# main_shema.net
KiCad netlist of a schematic drawn in EAGLE
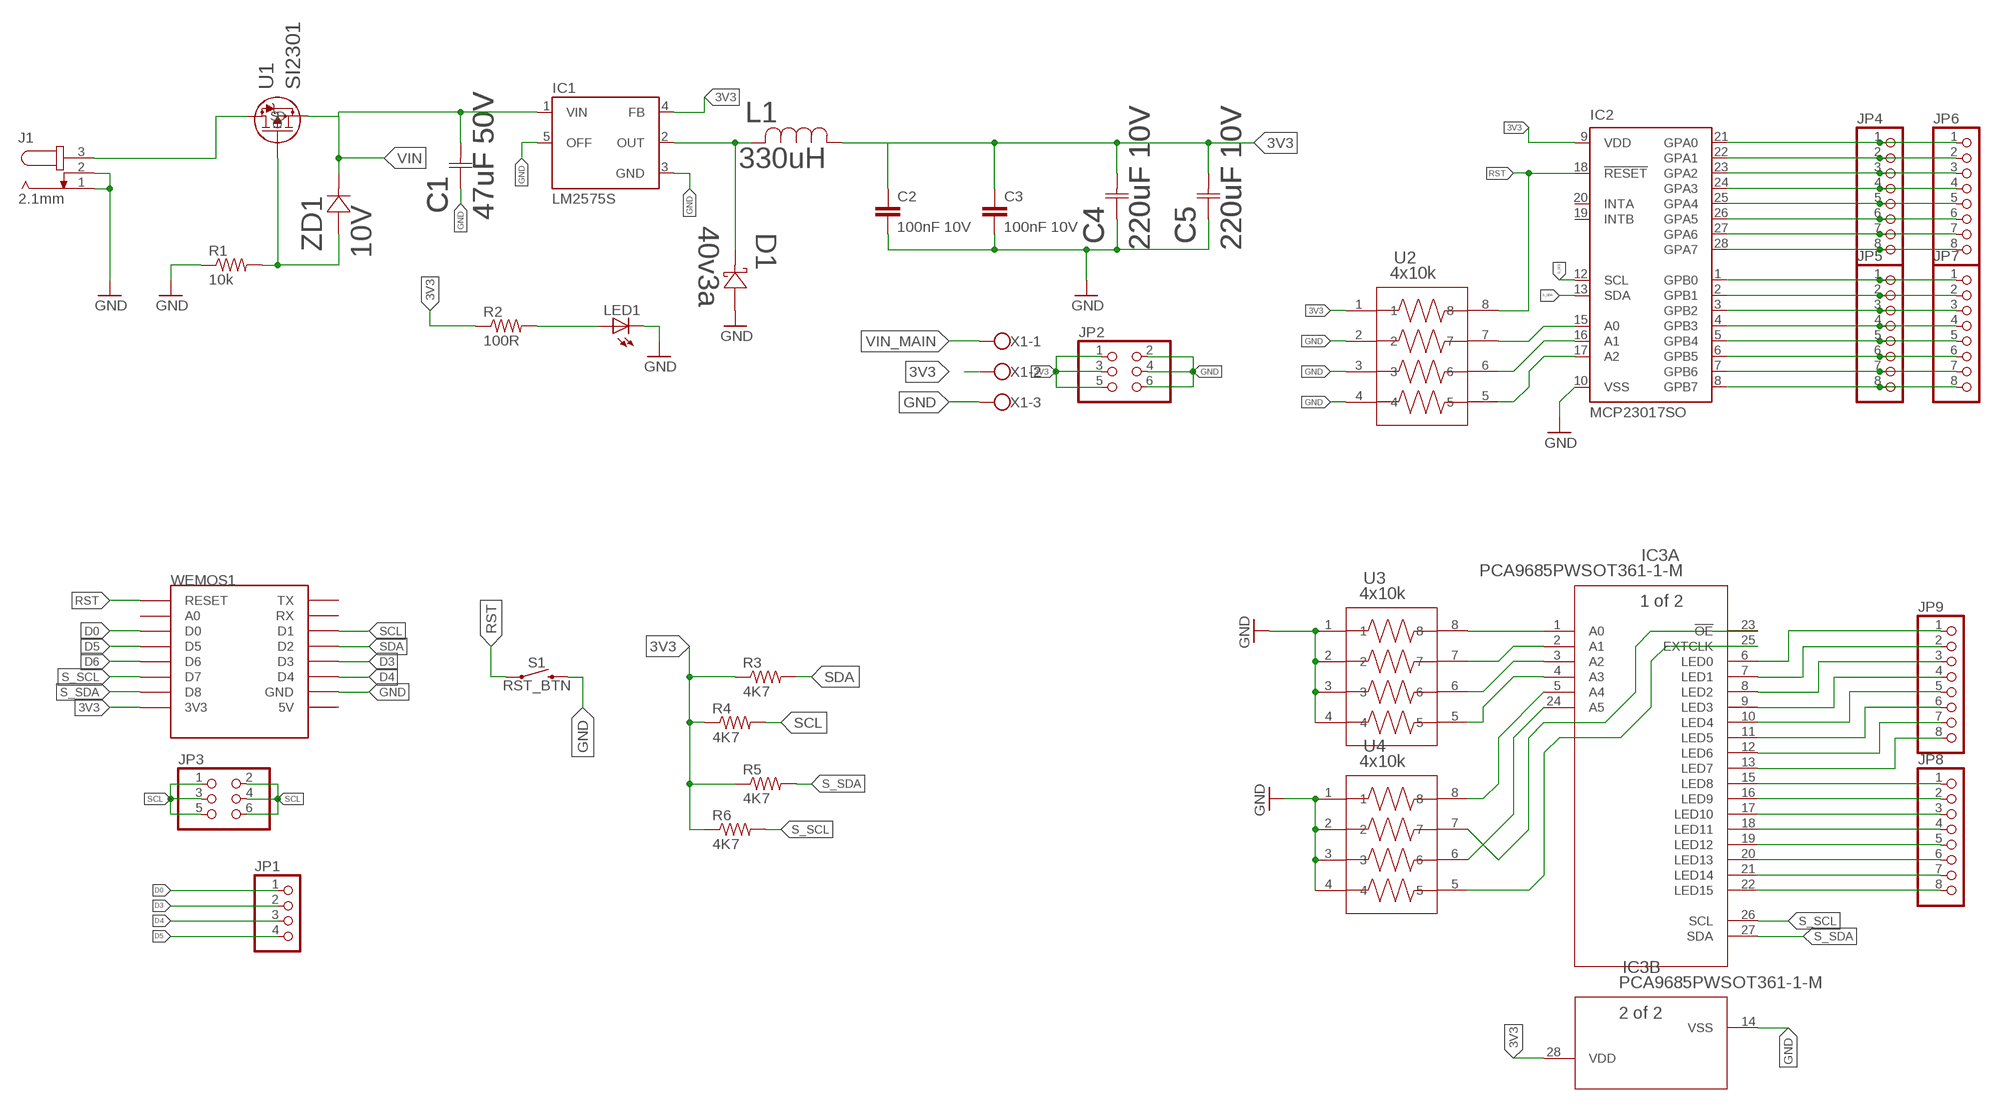
[diagram p0: schematic, sheet 1, part 1 of 2]
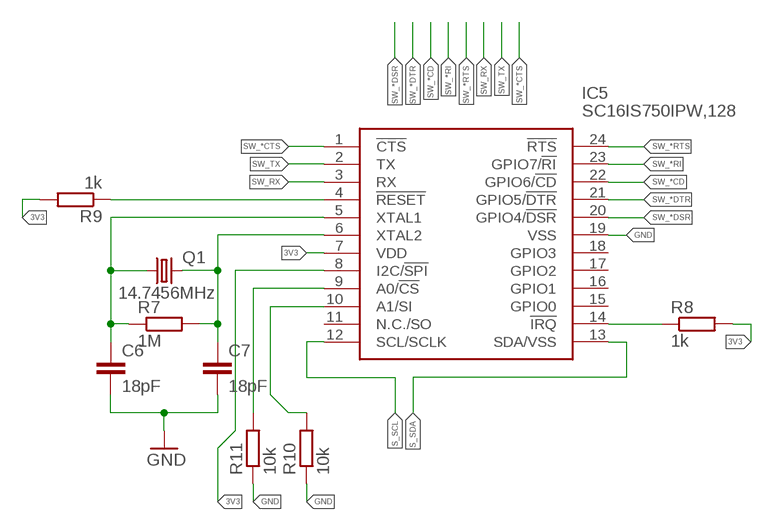
[diagram p1: schematic, sheet 1, part 2 of 2]

(export (version "E")
  (design (tool "Eeschema 10.0.6"))
  (components
    (comp (ref "C1")
      (value "47uF 50V")
      (footprint "eagle-import:CAP_EEE_D8-M")
      (fields (field (name "MANUFACTURER_PART_NUMBER") "EEE1HA470XP"))
      (libsource (lib "eagle-import") (part "EEE-1HA470XPCAP_EEE_D8-M"))
    )
    (comp (ref "C2")
      (value "100nF 10V")
      (footprint "eagle-import:C0603")
      (libsource (lib "eagle-import") (part "C-EUC0603"))
    )
    (comp (ref "C3")
      (value "100nF 10V")
      (footprint "eagle-import:C0603")
      (libsource (lib "eagle-import") (part "C-EUC0603"))
    )
    (comp (ref "C4")
      (value "220uF 10V")
      (footprint "eagle-import:CAP_EEE_D-M")
      (fields (field (name "MANUFACTURER_PART_NUMBER") "EEE0JA221WP"))
      (libsource (lib "eagle-import") (part "EEE-0JA221WPCAP_EEE_D-M"))
    )
    (comp (ref "C5")
      (value "220uF 10V")
      (footprint "eagle-import:CAP_EEE_D-M")
      (fields (field (name "MANUFACTURER_PART_NUMBER") "EEE0JA221WP"))
      (libsource (lib "eagle-import") (part "EEE-0JA221WPCAP_EEE_D-M"))
    )
    (comp (ref "C6")
      (value "18pF")
      (footprint "eagle-import:0402-CAP")
      (libsource (lib "eagle-import") (part "CAP0402-CAP"))
    )
    (comp (ref "C7")
      (value "18pF")
      (footprint "eagle-import:0402-CAP")
      (libsource (lib "eagle-import") (part "CAP0402-CAP"))
    )
    (comp (ref "D1")
      (value "40v3a")
      (footprint "eagle-import:CDBA-HF-M")
      (fields (field (name "MANUFACTURER_PART_NUMBER") "CDBA340HF"))
      (libsource (lib "eagle-import") (part "CDBA340-HFCDBA-HF-M"))
    )
    (comp (ref "IC1")
      (value "LM2575S")
      (footprint "eagle-import:TO263-5")
      (libsource (lib "eagle-import") (part "LM2575S"))
    )
    (comp (ref "IC2")
      (value "MCP23017SO")
      (footprint "eagle-import:SO28W")
      (fields (field (name "MF") "MICROCHIP") (field (name "MPN") "MCP23017-E/SO"))
      (libsource (lib "eagle-import") (part "MCP23017SO"))
    )
    (comp (ref "IC3")
      (value "PCA9685PWSOT361-1-M")
      (footprint "eagle-import:SOT361-1-M")
      (fields (field (name "MANUFACTURER_PART_NUMBER") "PCA9685PW"))
      (libsource (lib "eagle-import") (part "PCA9685PWSOT361-1-M"))
    )
    (comp (ref "IC5")
      (value "SC16IS750IPW,128")
      (footprint "eagle-import:SOP65P640X110-24N")
      (libsource (lib "eagle-import") (part "SC16IS750IPW,128"))
    )
    (comp (ref "J1")
      (value "2.1mm")
      (footprint "eagle-import:SPC4078")
      (libsource (lib "eagle-import") (part "JACK-PLUG1"))
    )
    (comp (ref "JP1")
      (value "PINHD-1X4")
      (footprint "eagle-import:1X04")
      (libsource (lib "eagle-import") (part "PINHD-1X4"))
    )
    (comp (ref "JP2")
      (value "PINHD-2X3")
      (footprint "eagle-import:2X03")
      (libsource (lib "eagle-import") (part "PINHD-2X3"))
    )
    (comp (ref "JP3")
      (value "PINHD-2X3")
      (footprint "eagle-import:2X03")
      (libsource (lib "eagle-import") (part "PINHD-2X3"))
    )
    (comp (ref "JP4")
      (value "PINHD-1X8")
      (footprint "eagle-import:1X08")
      (libsource (lib "eagle-import") (part "PINHD-1X8"))
    )
    (comp (ref "JP5")
      (value "PINHD-1X8")
      (footprint "eagle-import:1X08")
      (libsource (lib "eagle-import") (part "PINHD-1X8"))
    )
    (comp (ref "JP6")
      (value "PINHD-1X8")
      (footprint "eagle-import:1X08")
      (libsource (lib "eagle-import") (part "PINHD-1X8"))
    )
    (comp (ref "JP7")
      (value "PINHD-1X8")
      (footprint "eagle-import:1X08")
      (libsource (lib "eagle-import") (part "PINHD-1X8"))
    )
    (comp (ref "JP8")
      (value "PINHD-1X8/LONG")
      (footprint "eagle-import:1X08")
      (libsource (lib "eagle-import") (part "PINHD-1X8/LONG"))
    )
    (comp (ref "JP9")
      (value "PINHD-1X8/LONG")
      (footprint "eagle-import:1X08")
      (libsource (lib "eagle-import") (part "PINHD-1X8/LONG"))
    )
    (comp (ref "L1")
      (value "330uH")
      (footprint "eagle-import:IND_BOURNS_SRR1280")
      (fields (field (name "MANUFACTURER_PART_NUMBER") "SRR1280331K"))
      (libsource (lib "eagle-import") (part "SRR1280-331K"))
    )
    (comp (ref "LED1")
      (value "LED_E")
      (footprint "eagle-import:LED_1206")
      (libsource (lib "eagle-import") (part "LED_E"))
    )
    (comp (ref "Q1")
      (value "14.7456MHz")
      (footprint "eagle-import:CRYSTAL-SMD-5X3")
      (libsource (lib "eagle-import") (part "CRYSTAL5X3"))
    )
    (comp (ref "R1")
      (value "10k")
      (footprint "eagle-import:R0603")
      (libsource (lib "eagle-import") (part "R-US_R0603"))
    )
    (comp (ref "R2")
      (value "100R")
      (footprint "eagle-import:R0603")
      (libsource (lib "eagle-import") (part "R-US_R0603"))
    )
    (comp (ref "R3")
      (value "4K7")
      (footprint "eagle-import:R0603")
      (libsource (lib "eagle-import") (part "R-US_R0603"))
    )
    (comp (ref "R4")
      (value "4K7")
      (footprint "eagle-import:R0603")
      (libsource (lib "eagle-import") (part "R-US_R0603"))
    )
    (comp (ref "R5")
      (value "4K7")
      (footprint "eagle-import:R0603")
      (libsource (lib "eagle-import") (part "R-US_R0603"))
    )
    (comp (ref "R6")
      (value "4K7")
      (footprint "eagle-import:R0603")
      (libsource (lib "eagle-import") (part "R-US_R0603"))
    )
    (comp (ref "R7")
      (value "1M")
      (footprint "eagle-import:R0402")
      (libsource (lib "eagle-import") (part "R-EU_R0402"))
    )
    (comp (ref "R8")
      (value "1k")
      (footprint "eagle-import:R0402")
      (libsource (lib "eagle-import") (part "R-EU_R0402"))
    )
    (comp (ref "R9")
      (value "1k")
      (footprint "eagle-import:R0402")
      (libsource (lib "eagle-import") (part "R-EU_R0402"))
    )
    (comp (ref "R10")
      (value "10k")
      (footprint "eagle-import:R0402")
      (libsource (lib "eagle-import") (part "R-EU_R0402"))
    )
    (comp (ref "R11")
      (value "10k")
      (footprint "eagle-import:R0402")
      (libsource (lib "eagle-import") (part "R-EU_R0402"))
    )
    (comp (ref "S1")
      (value "RST_BTN")
      (footprint "eagle-import:TACTILE_SWITCH_PTH_6.0MM")
      (libsource (lib "eagle-import") (part "MOMENTARY-SWITCH-SPST-PTH-6.0MM"))
    )
    (comp (ref "U1")
      (value "SI2301")
      (footprint "eagle-import:TO-236-M")
      (fields (field (name "MANUFACTURER_PART_NUMBER") "SI2301CDST1GE3"))
      (libsource (lib "eagle-import") (part "SI2301CDS-T1-GE3TO-236-M"))
    )
    (comp (ref "U2")
      (value "4x10k")
      (footprint "eagle-import:C_ARRAY_EXB38V")
      (fields (field (name "MANUFACTURER_PART_NUMBER") "EXB38V103JV"))
      (libsource (lib "eagle-import") (part "EXB-38V103JV"))
    )
    (comp (ref "U3")
      (value "4x10k")
      (footprint "eagle-import:C_ARRAY_EXB38V-M")
      (fields (field (name "MANUFACTURER_PART_NUMBER") "EXB38V103JV"))
      (libsource (lib "eagle-import") (part "EXB-38V103JVC_ARRAY_EXB38V-M"))
    )
    (comp (ref "U4")
      (value "4x10k")
      (footprint "eagle-import:C_ARRAY_EXB38V-M")
      (fields (field (name "MANUFACTURER_PART_NUMBER") "EXB38V103JV"))
      (libsource (lib "eagle-import") (part "EXB-38V103JVC_ARRAY_EXB38V-M"))
    )
    (comp (ref "WEMOS1")
      (value "WEMOS-D1-MINI")
      (footprint "eagle-import:WEMOS-D1-MINI")
      (libsource (lib "eagle-import") (part "WEMOS-D1-MINI"))
    )
    (comp (ref "X1")
      (value "W237-103")
      (footprint "eagle-import:W237-103")
      (fields (field (name "MPN") "237-103"))
      (libsource (lib "eagle-import") (part "W237-103"))
    )
    (comp (ref "ZD1")
      (value "10V")
      (footprint "eagle-import:SMINI2-F5-B-M")
      (fields (field (name "MANUFACTURER_PART_NUMBER") "DZ2J100M0L"))
      (libsource (lib "eagle-import") (part "DZ2J100M0LSMINI2-F5-B-M"))
    )
  )
  (nets
    (net (code "1") (name "3V3") (class "Default")
      (node (ref "C2") (pin "1") (pinfunction "1_1") (pintype "passive"))
      (node (ref "C3") (pin "1") (pinfunction "1_1") (pintype "passive"))
      (node (ref "C4") (pin "2") (pinfunction "22_2") (pintype "passive"))
      (node (ref "C5") (pin "2") (pinfunction "22_2") (pintype "passive"))
      (node (ref "IC1") (pin "4") (pinfunction "FB_4") (pintype "input"))
      (node (ref "IC2") (pin "9") (pinfunction "VDD_9") (pintype "power_in"))
      (node (ref "IC3") (pin "28") (pinfunction "VDD_28") (pintype "passive"))
      (node (ref "IC5") (pin "7") (pinfunction "VDD_7") (pintype "power_in"))
      (node (ref "IC5") (pin "8") (pinfunction "I2C/~{SPI}_8") (pintype "bidirectional"))
      (node (ref "JP2") (pin "1") (pinfunction "1_1") (pintype "passive"))
      (node (ref "JP2") (pin "3") (pinfunction "3_3") (pintype "passive"))
      (node (ref "JP2") (pin "5") (pinfunction "5_5") (pintype "passive"))
      (node (ref "L1") (pin "1") (pinfunction "1_1") (pintype "passive"))
      (node (ref "R2") (pin "1") (pinfunction "1_1") (pintype "passive"))
      (node (ref "R3") (pin "1") (pinfunction "1_1") (pintype "passive"))
      (node (ref "R4") (pin "1") (pinfunction "1_1") (pintype "passive"))
      (node (ref "R5") (pin "1") (pinfunction "1_1") (pintype "passive"))
      (node (ref "R6") (pin "1") (pinfunction "1_1") (pintype "passive"))
      (node (ref "R8") (pin "2") (pinfunction "2_2") (pintype "passive"))
      (node (ref "R9") (pin "2") (pinfunction "2_2") (pintype "passive"))
      (node (ref "U2") (pin "1") (pinfunction "1_1") (pintype "passive"))
      (node (ref "WEMOS1") (pin "3V3") (pinfunction "3V3_3V3") (pintype "bidirectional"))
      (node (ref "X1") (pin "2") (pinfunction "KL_2") (pintype "passive"))
    )
    (net (code "2") (name "D0") (class "Default")
      (node (ref "JP1") (pin "1") (pinfunction "1_1") (pintype "passive"))
      (node (ref "WEMOS1") (pin "D0") (pinfunction "D0_D0") (pintype "bidirectional"))
    )
    (net (code "3") (name "D3") (class "Default")
      (node (ref "JP1") (pin "2") (pinfunction "2_2") (pintype "passive"))
      (node (ref "WEMOS1") (pin "D3") (pinfunction "D3_D3") (pintype "bidirectional"))
    )
    (net (code "4") (name "D4") (class "Default")
      (node (ref "JP1") (pin "3") (pinfunction "3_3") (pintype "passive"))
      (node (ref "WEMOS1") (pin "D4") (pinfunction "D4_D4") (pintype "bidirectional"))
    )
    (net (code "5") (name "D5") (class "Default")
      (node (ref "JP1") (pin "4") (pinfunction "4_4") (pintype "passive"))
      (node (ref "WEMOS1") (pin "D5") (pinfunction "D5_D5") (pintype "bidirectional"))
    )
    (net (code "6") (name "D6") (class "Default")
      (node (ref "WEMOS1") (pin "D6") (pinfunction "D6_D6") (pintype "bidirectional"))
    )
    (net (code "7") (name "GND") (class "Default")
      (node (ref "C1") (pin "1") (pinfunction "11_1") (pintype "passive"))
      (node (ref "C2") (pin "2") (pinfunction "2_2") (pintype "passive"))
      (node (ref "C3") (pin "2") (pinfunction "2_2") (pintype "passive"))
      (node (ref "C4") (pin "1") (pinfunction "11_1") (pintype "passive"))
      (node (ref "C5") (pin "1") (pinfunction "11_1") (pintype "passive"))
      (node (ref "C6") (pin "2") (pinfunction "2_2") (pintype "passive"))
      (node (ref "C7") (pin "2") (pinfunction "2_2") (pintype "passive"))
      (node (ref "D1") (pin "2") (pinfunction "22_2") (pintype "passive"))
      (node (ref "IC1") (pin "3") (pinfunction "GND_3") (pintype "power_in"))
      (node (ref "IC1") (pin "5") (pinfunction "OFF_5") (pintype "input"))
      (node (ref "IC2") (pin "10") (pinfunction "VSS_10") (pintype "power_in"))
      (node (ref "IC3") (pin "14") (pinfunction "VSS_14") (pintype "passive"))
      (node (ref "IC5") (pin "19") (pinfunction "VSS_19") (pintype "bidirectional"))
      (node (ref "J1") (pin "1") (pinfunction "1_1") (pintype "passive"))
      (node (ref "J1") (pin "2") (pinfunction "2_2") (pintype "passive"))
      (node (ref "JP2") (pin "2") (pinfunction "2_2") (pintype "passive"))
      (node (ref "JP2") (pin "4") (pinfunction "4_4") (pintype "passive"))
      (node (ref "JP2") (pin "6") (pinfunction "6_6") (pintype "passive"))
      (node (ref "LED1") (pin "C") (pinfunction "C_C") (pintype "passive"))
      (node (ref "R1") (pin "1") (pinfunction "1_1") (pintype "passive"))
      (node (ref "R10") (pin "1") (pinfunction "1_1") (pintype "passive"))
      (node (ref "R11") (pin "1") (pinfunction "1_1") (pintype "passive"))
      (node (ref "S1") (pin "3") (pinfunction "2_3") (pintype "passive"))
      (node (ref "U2") (pin "2") (pinfunction "2_2") (pintype "passive"))
      (node (ref "U2") (pin "3") (pinfunction "3_3") (pintype "passive"))
      (node (ref "U2") (pin "4") (pinfunction "4_4") (pintype "passive"))
      (node (ref "U3") (pin "1") (pinfunction "1_1") (pintype "passive"))
      (node (ref "U3") (pin "2") (pinfunction "2_2") (pintype "passive"))
      (node (ref "U3") (pin "3") (pinfunction "3_3") (pintype "passive"))
      (node (ref "U3") (pin "4") (pinfunction "4_4") (pintype "passive"))
      (node (ref "U4") (pin "1") (pinfunction "1_1") (pintype "passive"))
      (node (ref "U4") (pin "2") (pinfunction "2_2") (pintype "passive"))
      (node (ref "U4") (pin "3") (pinfunction "3_3") (pintype "passive"))
      (node (ref "U4") (pin "4") (pinfunction "4_4") (pintype "passive"))
      (node (ref "WEMOS1") (pin "GND") (pinfunction "GND_GND") (pintype "bidirectional"))
      (node (ref "X1") (pin "3") (pinfunction "KL_3") (pintype "passive"))
    )
    (net (code "8") (name "Net-(D1-11)") (class "Default")
      (node (ref "D1") (pin "1") (pinfunction "11_1") (pintype "passive"))
      (node (ref "IC1") (pin "2") (pinfunction "OUT_2") (pintype "output"))
      (node (ref "L1") (pin "2") (pinfunction "2_2") (pintype "passive"))
    )
    (net (code "9") (name "Net-(IC2-A0)") (class "Default")
      (node (ref "IC2") (pin "15") (pinfunction "A0_15") (pintype "input"))
      (node (ref "U2") (pin "7") (pinfunction "7_7") (pintype "passive"))
    )
    (net (code "10") (name "Net-(IC2-A1)") (class "Default")
      (node (ref "IC2") (pin "16") (pinfunction "A1_16") (pintype "input"))
      (node (ref "U2") (pin "6") (pinfunction "6_6") (pintype "passive"))
    )
    (net (code "11") (name "Net-(IC2-A2)") (class "Default")
      (node (ref "IC2") (pin "17") (pinfunction "A2_17") (pintype "input"))
      (node (ref "U2") (pin "5") (pinfunction "5_5") (pintype "passive"))
    )
    (net (code "12") (name "Net-(IC2-GPA0)") (class "Default")
      (node (ref "IC2") (pin "21") (pinfunction "GPA0_21") (pintype "bidirectional"))
      (node (ref "JP4") (pin "1") (pinfunction "1_1") (pintype "passive"))
      (node (ref "JP6") (pin "1") (pinfunction "1_1") (pintype "passive"))
    )
    (net (code "13") (name "Net-(IC2-GPA1)") (class "Default")
      (node (ref "IC2") (pin "22") (pinfunction "GPA1_22") (pintype "bidirectional"))
      (node (ref "JP4") (pin "2") (pinfunction "2_2") (pintype "passive"))
      (node (ref "JP6") (pin "2") (pinfunction "2_2") (pintype "passive"))
    )
    (net (code "14") (name "Net-(IC2-GPA2)") (class "Default")
      (node (ref "IC2") (pin "23") (pinfunction "GPA2_23") (pintype "bidirectional"))
      (node (ref "JP4") (pin "3") (pinfunction "3_3") (pintype "passive"))
      (node (ref "JP6") (pin "3") (pinfunction "3_3") (pintype "passive"))
    )
    (net (code "15") (name "Net-(IC2-GPA3)") (class "Default")
      (node (ref "IC2") (pin "24") (pinfunction "GPA3_24") (pintype "bidirectional"))
      (node (ref "JP4") (pin "4") (pinfunction "4_4") (pintype "passive"))
      (node (ref "JP6") (pin "4") (pinfunction "4_4") (pintype "passive"))
    )
    (net (code "16") (name "Net-(IC2-GPA4)") (class "Default")
      (node (ref "IC2") (pin "25") (pinfunction "GPA4_25") (pintype "bidirectional"))
      (node (ref "JP4") (pin "5") (pinfunction "5_5") (pintype "passive"))
      (node (ref "JP6") (pin "5") (pinfunction "5_5") (pintype "passive"))
    )
    (net (code "17") (name "Net-(IC2-GPA5)") (class "Default")
      (node (ref "IC2") (pin "26") (pinfunction "GPA5_26") (pintype "bidirectional"))
      (node (ref "JP4") (pin "6") (pinfunction "6_6") (pintype "passive"))
      (node (ref "JP6") (pin "6") (pinfunction "6_6") (pintype "passive"))
    )
    (net (code "18") (name "Net-(IC2-GPA6)") (class "Default")
      (node (ref "IC2") (pin "27") (pinfunction "GPA6_27") (pintype "bidirectional"))
      (node (ref "JP4") (pin "7") (pinfunction "7_7") (pintype "passive"))
      (node (ref "JP6") (pin "7") (pinfunction "7_7") (pintype "passive"))
    )
    (net (code "19") (name "Net-(IC2-GPA7)") (class "Default")
      (node (ref "IC2") (pin "28") (pinfunction "GPA7_28") (pintype "bidirectional"))
      (node (ref "JP4") (pin "8") (pinfunction "8_8") (pintype "passive"))
      (node (ref "JP6") (pin "8") (pinfunction "8_8") (pintype "passive"))
    )
    (net (code "20") (name "Net-(IC2-GPB0)") (class "Default")
      (node (ref "IC2") (pin "1") (pinfunction "GPB0_1") (pintype "bidirectional"))
      (node (ref "JP5") (pin "1") (pinfunction "1_1") (pintype "passive"))
      (node (ref "JP7") (pin "1") (pinfunction "1_1") (pintype "passive"))
    )
    (net (code "21") (name "Net-(IC2-GPB1)") (class "Default")
      (node (ref "IC2") (pin "2") (pinfunction "GPB1_2") (pintype "bidirectional"))
      (node (ref "JP5") (pin "2") (pinfunction "2_2") (pintype "passive"))
      (node (ref "JP7") (pin "2") (pinfunction "2_2") (pintype "passive"))
    )
    (net (code "22") (name "Net-(IC2-GPB2)") (class "Default")
      (node (ref "IC2") (pin "3") (pinfunction "GPB2_3") (pintype "bidirectional"))
      (node (ref "JP5") (pin "3") (pinfunction "3_3") (pintype "passive"))
      (node (ref "JP7") (pin "3") (pinfunction "3_3") (pintype "passive"))
    )
    (net (code "23") (name "Net-(IC2-GPB3)") (class "Default")
      (node (ref "IC2") (pin "4") (pinfunction "GPB3_4") (pintype "bidirectional"))
      (node (ref "JP5") (pin "4") (pinfunction "4_4") (pintype "passive"))
      (node (ref "JP7") (pin "4") (pinfunction "4_4") (pintype "passive"))
    )
    (net (code "24") (name "Net-(IC2-GPB4)") (class "Default")
      (node (ref "IC2") (pin "5") (pinfunction "GPB4_5") (pintype "bidirectional"))
      (node (ref "JP5") (pin "5") (pinfunction "5_5") (pintype "passive"))
      (node (ref "JP7") (pin "5") (pinfunction "5_5") (pintype "passive"))
    )
    (net (code "25") (name "Net-(IC2-GPB5)") (class "Default")
      (node (ref "IC2") (pin "6") (pinfunction "GPB5_6") (pintype "bidirectional"))
      (node (ref "JP5") (pin "6") (pinfunction "6_6") (pintype "passive"))
      (node (ref "JP7") (pin "6") (pinfunction "6_6") (pintype "passive"))
    )
    (net (code "26") (name "Net-(IC2-GPB6)") (class "Default")
      (node (ref "IC2") (pin "7") (pinfunction "GPB6_7") (pintype "bidirectional"))
      (node (ref "JP5") (pin "7") (pinfunction "7_7") (pintype "passive"))
      (node (ref "JP7") (pin "7") (pinfunction "7_7") (pintype "passive"))
    )
    (net (code "27") (name "Net-(IC2-GPB7)") (class "Default")
      (node (ref "IC2") (pin "8") (pinfunction "GPB7_8") (pintype "bidirectional"))
      (node (ref "JP5") (pin "8") (pinfunction "8_8") (pintype "passive"))
      (node (ref "JP7") (pin "8") (pinfunction "8_8") (pintype "passive"))
    )
    (net (code "28") (name "Net-(IC3A-A0)") (class "Default")
      (node (ref "IC3") (pin "1") (pinfunction "A0_1") (pintype "passive"))
      (node (ref "U3") (pin "8") (pinfunction "8_8") (pintype "passive"))
    )
    (net (code "29") (name "Net-(IC3A-A1)") (class "Default")
      (node (ref "IC3") (pin "2") (pinfunction "A1_2") (pintype "passive"))
      (node (ref "U3") (pin "7") (pinfunction "7_7") (pintype "passive"))
    )
    (net (code "30") (name "Net-(IC3A-A2)") (class "Default")
      (node (ref "IC3") (pin "3") (pinfunction "A2_3") (pintype "passive"))
      (node (ref "U3") (pin "6") (pinfunction "6_6") (pintype "passive"))
    )
    (net (code "31") (name "Net-(IC3A-A3)") (class "Default")
      (node (ref "IC3") (pin "4") (pinfunction "A3_4") (pintype "passive"))
      (node (ref "U3") (pin "5") (pinfunction "5_5") (pintype "passive"))
    )
    (net (code "32") (name "Net-(IC3A-A4)") (class "Default")
      (node (ref "IC3") (pin "5") (pinfunction "A4_5") (pintype "passive"))
      (node (ref "U4") (pin "8") (pinfunction "8_8") (pintype "passive"))
    )
    (net (code "33") (name "Net-(IC3A-A5)") (class "Default")
      (node (ref "IC3") (pin "24") (pinfunction "A5_24") (pintype "passive"))
      (node (ref "U4") (pin "6") (pinfunction "6_6") (pintype "passive"))
    )
    (net (code "34") (name "Net-(IC3A-EXTCLK)") (class "Default")
      (node (ref "IC3") (pin "25") (pinfunction "EXTCLK_25") (pintype "passive"))
      (node (ref "U4") (pin "5") (pinfunction "5_5") (pintype "passive"))
    )
    (net (code "35") (name "Net-(IC3A-LED0)") (class "Default")
      (node (ref "IC3") (pin "6") (pinfunction "LED0_6") (pintype "passive"))
      (node (ref "JP9") (pin "1") (pinfunction "1_1") (pintype "passive"))
    )
    (net (code "36") (name "Net-(IC3A-LED1)") (class "Default")
      (node (ref "IC3") (pin "7") (pinfunction "LED1_7") (pintype "passive"))
      (node (ref "JP9") (pin "2") (pinfunction "2_2") (pintype "passive"))
    )
    (net (code "37") (name "Net-(IC3A-LED2)") (class "Default")
      (node (ref "IC3") (pin "8") (pinfunction "LED2_8") (pintype "passive"))
      (node (ref "JP9") (pin "3") (pinfunction "3_3") (pintype "passive"))
    )
    (net (code "38") (name "Net-(IC3A-LED3)") (class "Default")
      (node (ref "IC3") (pin "9") (pinfunction "LED3_9") (pintype "passive"))
      (node (ref "JP9") (pin "4") (pinfunction "4_4") (pintype "passive"))
    )
    (net (code "39") (name "Net-(IC3A-LED4)") (class "Default")
      (node (ref "IC3") (pin "10") (pinfunction "LED4_10") (pintype "passive"))
      (node (ref "JP9") (pin "5") (pinfunction "5_5") (pintype "passive"))
    )
    (net (code "40") (name "Net-(IC3A-LED5)") (class "Default")
      (node (ref "IC3") (pin "11") (pinfunction "LED5_11") (pintype "passive"))
      (node (ref "JP9") (pin "6") (pinfunction "6_6") (pintype "passive"))
    )
    (net (code "41") (name "Net-(IC3A-LED6)") (class "Default")
      (node (ref "IC3") (pin "12") (pinfunction "LED6_12") (pintype "passive"))
      (node (ref "JP9") (pin "7") (pinfunction "7_7") (pintype "passive"))
    )
    (net (code "42") (name "Net-(IC3A-LED7)") (class "Default")
      (node (ref "IC3") (pin "13") (pinfunction "LED7_13") (pintype "passive"))
      (node (ref "JP9") (pin "8") (pinfunction "8_8") (pintype "passive"))
    )
    (net (code "43") (name "Net-(IC3A-LED8)") (class "Default")
      (node (ref "IC3") (pin "15") (pinfunction "LED8_15") (pintype "passive"))
      (node (ref "JP8") (pin "1") (pinfunction "1_1") (pintype "passive"))
    )
    (net (code "44") (name "Net-(IC3A-LED9)") (class "Default")
      (node (ref "IC3") (pin "16") (pinfunction "LED9_16") (pintype "passive"))
      (node (ref "JP8") (pin "2") (pinfunction "2_2") (pintype "passive"))
    )
    (net (code "45") (name "Net-(IC3A-LED10)") (class "Default")
      (node (ref "IC3") (pin "17") (pinfunction "LED10_17") (pintype "passive"))
      (node (ref "JP8") (pin "3") (pinfunction "3_3") (pintype "passive"))
    )
    (net (code "46") (name "Net-(IC3A-LED11)") (class "Default")
      (node (ref "IC3") (pin "18") (pinfunction "LED11_18") (pintype "passive"))
      (node (ref "JP8") (pin "4") (pinfunction "4_4") (pintype "passive"))
    )
    (net (code "47") (name "Net-(IC3A-LED12)") (class "Default")
      (node (ref "IC3") (pin "19") (pinfunction "LED12_19") (pintype "passive"))
      (node (ref "JP8") (pin "5") (pinfunction "5_5") (pintype "passive"))
    )
    (net (code "48") (name "Net-(IC3A-LED13)") (class "Default")
      (node (ref "IC3") (pin "20") (pinfunction "LED13_20") (pintype "passive"))
      (node (ref "JP8") (pin "6") (pinfunction "6_6") (pintype "passive"))
    )
    (net (code "49") (name "Net-(IC3A-LED14)") (class "Default")
      (node (ref "IC3") (pin "21") (pinfunction "LED14_21") (pintype "passive"))
      (node (ref "JP8") (pin "7") (pinfunction "7_7") (pintype "passive"))
    )
    (net (code "50") (name "Net-(IC3A-LED15)") (class "Default")
      (node (ref "IC3") (pin "22") (pinfunction "LED15_22") (pintype "passive"))
      (node (ref "JP8") (pin "8") (pinfunction "8_8") (pintype "passive"))
    )
    (net (code "51") (name "Net-(IC3A-~{OE})") (class "Default")
      (node (ref "IC3") (pin "23") (pinfunction "~{OE}_23") (pintype "passive"))
      (node (ref "U4") (pin "7") (pinfunction "7_7") (pintype "passive"))
    )
    (net (code "52") (name "Net-(IC5-A0{slash}~{CS})") (class "Default")
      (node (ref "IC5") (pin "9") (pinfunction "A0/~{CS}_9") (pintype "bidirectional"))
      (node (ref "R11") (pin "2") (pinfunction "2_2") (pintype "passive"))
    )
    (net (code "53") (name "Net-(IC5-A1{slash}SI)") (class "Default")
      (node (ref "IC5") (pin "10") (pinfunction "A1/SI_10") (pintype "bidirectional"))
      (node (ref "R10") (pin "2") (pinfunction "2_2") (pintype "passive"))
    )
    (net (code "54") (name "Net-(IC5-XTAL1)") (class "Default")
      (node (ref "C6") (pin "1") (pinfunction "1_1") (pintype "passive"))
      (node (ref "IC5") (pin "5") (pinfunction "XTAL1_5") (pintype "bidirectional"))
      (node (ref "Q1") (pin "1") (pinfunction "1_1") (pintype "passive"))
      (node (ref "R7") (pin "1") (pinfunction "1_1") (pintype "passive"))
    )
    (net (code "55") (name "Net-(IC5-XTAL2)") (class "Default")
      (node (ref "C7") (pin "1") (pinfunction "1_1") (pintype "passive"))
      (node (ref "IC5") (pin "6") (pinfunction "XTAL2_6") (pintype "bidirectional"))
      (node (ref "Q1") (pin "3") (pinfunction "2_3") (pintype "passive"))
      (node (ref "R7") (pin "2") (pinfunction "2_2") (pintype "passive"))
    )
    (net (code "56") (name "Net-(IC5-~{IRQ})") (class "Default")
      (node (ref "IC5") (pin "14") (pinfunction "~{IRQ}_14") (pintype "bidirectional"))
      (node (ref "R8") (pin "1") (pinfunction "1_1") (pintype "passive"))
    )
    (net (code "57") (name "Net-(IC5-~{RESET})") (class "Default")
      (node (ref "IC5") (pin "4") (pinfunction "~{RESET}_4") (pintype "input"))
      (node (ref "R9") (pin "1") (pinfunction "1_1") (pintype "passive"))
    )
    (net (code "58") (name "Net-(LED1-PadA)") (class "Default")
      (node (ref "LED1") (pin "A") (pinfunction "A_A") (pintype "passive"))
      (node (ref "R2") (pin "2") (pinfunction "2_2") (pintype "passive"))
    )
    (net (code "59") (name "Net-(U1-G)") (class "Default")
      (node (ref "R1") (pin "2") (pinfunction "2_2") (pintype "passive"))
      (node (ref "U1") (pin "1") (pinfunction "G_1") (pintype "passive"))
      (node (ref "ZD1") (pin "2") (pinfunction "22_2") (pintype "passive"))
    )
    (net (code "60") (name "RST") (class "Default")
      (node (ref "IC2") (pin "18") (pinfunction "~{RESET}_18") (pintype "input"))
      (node (ref "S1") (pin "1") (pinfunction "1_1") (pintype "passive"))
      (node (ref "U2") (pin "8") (pinfunction "8_8") (pintype "passive"))
      (node (ref "WEMOS1") (pin "RESET") (pinfunction "RESET_RESET") (pintype "bidirectional"))
    )
    (net (code "61") (name "SCL") (class "Default")
      (node (ref "JP3") (pin "1") (pinfunction "1_1") (pintype "passive"))
      (node (ref "JP3") (pin "3") (pinfunction "3_3") (pintype "passive"))
      (node (ref "JP3") (pin "5") (pinfunction "5_5") (pintype "passive"))
      (node (ref "R4") (pin "2") (pinfunction "2_2") (pintype "passive"))
      (node (ref "WEMOS1") (pin "D1") (pinfunction "D1_D1") (pintype "bidirectional"))
    )
    (net (code "62") (name "SDA") (class "Default")
      (node (ref "JP3") (pin "2") (pinfunction "2_2") (pintype "passive"))
      (node (ref "JP3") (pin "4") (pinfunction "4_4") (pintype "passive"))
      (node (ref "JP3") (pin "6") (pinfunction "6_6") (pintype "passive"))
      (node (ref "R3") (pin "2") (pinfunction "2_2") (pintype "passive"))
      (node (ref "WEMOS1") (pin "D2") (pinfunction "D2_D2") (pintype "bidirectional"))
    )
    (net (code "63") (name "SW_*CD") (class "Default")
      (node (ref "IC5") (pin "22") (pinfunction "GPIO6/~{CD}_22") (pintype "bidirectional"))
    )
    (net (code "64") (name "SW_*CTS") (class "Default")
      (node (ref "IC5") (pin "1") (pinfunction "~{CTS}_1") (pintype "bidirectional"))
    )
    (net (code "65") (name "SW_*DSR") (class "Default")
      (node (ref "IC5") (pin "20") (pinfunction "GPIO4/~{DSR}_20") (pintype "bidirectional"))
    )
    (net (code "66") (name "SW_*DTR") (class "Default")
      (node (ref "IC5") (pin "21") (pinfunction "GPIO5/~{DTR}_21") (pintype "bidirectional"))
    )
    (net (code "67") (name "SW_*RI") (class "Default")
      (node (ref "IC5") (pin "23") (pinfunction "GPIO7/~{RI}_23") (pintype "bidirectional"))
    )
    (net (code "68") (name "SW_*RTS") (class "Default")
      (node (ref "IC5") (pin "24") (pinfunction "~{RTS}_24") (pintype "bidirectional"))
    )
    (net (code "69") (name "SW_RX") (class "Default")
      (node (ref "IC5") (pin "3") (pinfunction "RX_3") (pintype "input"))
    )
    (net (code "70") (name "SW_TX") (class "Default")
      (node (ref "IC5") (pin "2") (pinfunction "TX_2") (pintype "input"))
    )
    (net (code "71") (name "S_SCL") (class "Default")
      (node (ref "IC2") (pin "12") (pinfunction "SCL_12") (pintype "input"))
      (node (ref "IC3") (pin "26") (pinfunction "SCL_26") (pintype "passive"))
      (node (ref "IC5") (pin "12") (pinfunction "SCL/SCLK_12") (pintype "bidirectional"))
      (node (ref "R6") (pin "2") (pinfunction "2_2") (pintype "passive"))
      (node (ref "WEMOS1") (pin "D7") (pinfunction "D7_D7") (pintype "bidirectional"))
    )
    (net (code "72") (name "S_SDA") (class "Default")
      (node (ref "IC2") (pin "13") (pinfunction "SDA_13") (pintype "bidirectional"))
      (node (ref "IC3") (pin "27") (pinfunction "SDA_27") (pintype "passive"))
      (node (ref "IC5") (pin "13") (pinfunction "SDA/VSS_13") (pintype "bidirectional"))
      (node (ref "R5") (pin "2") (pinfunction "2_2") (pintype "passive"))
      (node (ref "WEMOS1") (pin "D8") (pinfunction "D8_D8") (pintype "bidirectional"))
    )
    (net (code "73") (name "VIN") (class "Default")
      (node (ref "C1") (pin "2") (pinfunction "22_2") (pintype "passive"))
      (node (ref "IC1") (pin "1") (pinfunction "VIN_1") (pintype "power_in"))
      (node (ref "U1") (pin "2") (pinfunction "S_2") (pintype "passive"))
      (node (ref "ZD1") (pin "1") (pinfunction "11_1") (pintype "passive"))
    )
    (net (code "74") (name "VIN_MAIN") (class "Default")
      (node (ref "J1") (pin "3") (pinfunction "3_3") (pintype "passive"))
      (node (ref "U1") (pin "3") (pinfunction "D_3") (pintype "passive"))
      (node (ref "X1") (pin "1") (pinfunction "KL_1") (pintype "passive"))
    )
    (net (code "75") (name "unconnected-(IC2-INTA-Pad20)") (class "Default")
      (node (ref "IC2") (pin "20") (pinfunction "INTA_20") (pintype "output"))
    )
    (net (code "76") (name "unconnected-(IC2-INTB-Pad19)") (class "Default")
      (node (ref "IC2") (pin "19") (pinfunction "INTB_19") (pintype "output"))
    )
    (net (code "77") (name "unconnected-(IC5-GPIO0-Pad15)") (class "Default")
      (node (ref "IC5") (pin "15") (pinfunction "GPIO0_15") (pintype "bidirectional"))
    )
    (net (code "78") (name "unconnected-(IC5-GPIO1-Pad16)") (class "Default")
      (node (ref "IC5") (pin "16") (pinfunction "GPIO1_16") (pintype "bidirectional"))
    )
    (net (code "79") (name "unconnected-(IC5-GPIO2-Pad17)") (class "Default")
      (node (ref "IC5") (pin "17") (pinfunction "GPIO2_17") (pintype "bidirectional"))
    )
    (net (code "80") (name "unconnected-(IC5-GPIO3-Pad18)") (class "Default")
      (node (ref "IC5") (pin "18") (pinfunction "GPIO3_18") (pintype "bidirectional"))
    )
    (net (code "81") (name "unconnected-(IC5-N.C.{slash}SO-Pad11)") (class "Default")
      (node (ref "IC5") (pin "11") (pinfunction "N.C./SO_11") (pintype "bidirectional"))
    )
    (net (code "82") (name "unconnected-(WEMOS1-Pad5V)") (class "Default")
      (node (ref "WEMOS1") (pin "5V") (pinfunction "5V_5V") (pintype "bidirectional"))
    )
    (net (code "83") (name "unconnected-(WEMOS1-PadA0)") (class "Default")
      (node (ref "WEMOS1") (pin "A0") (pinfunction "A0_A0") (pintype "bidirectional"))
    )
    (net (code "84") (name "unconnected-(WEMOS1-PadRX)") (class "Default")
      (node (ref "WEMOS1") (pin "RX") (pinfunction "RX_RX") (pintype "bidirectional"))
    )
    (net (code "85") (name "unconnected-(WEMOS1-PadTX)") (class "Default")
      (node (ref "WEMOS1") (pin "TX") (pinfunction "TX_TX") (pintype "bidirectional"))
    )
  )
)
